# control_prg_03_12_2018.net
KiCad netlist of a schematic drawn in EAGLE
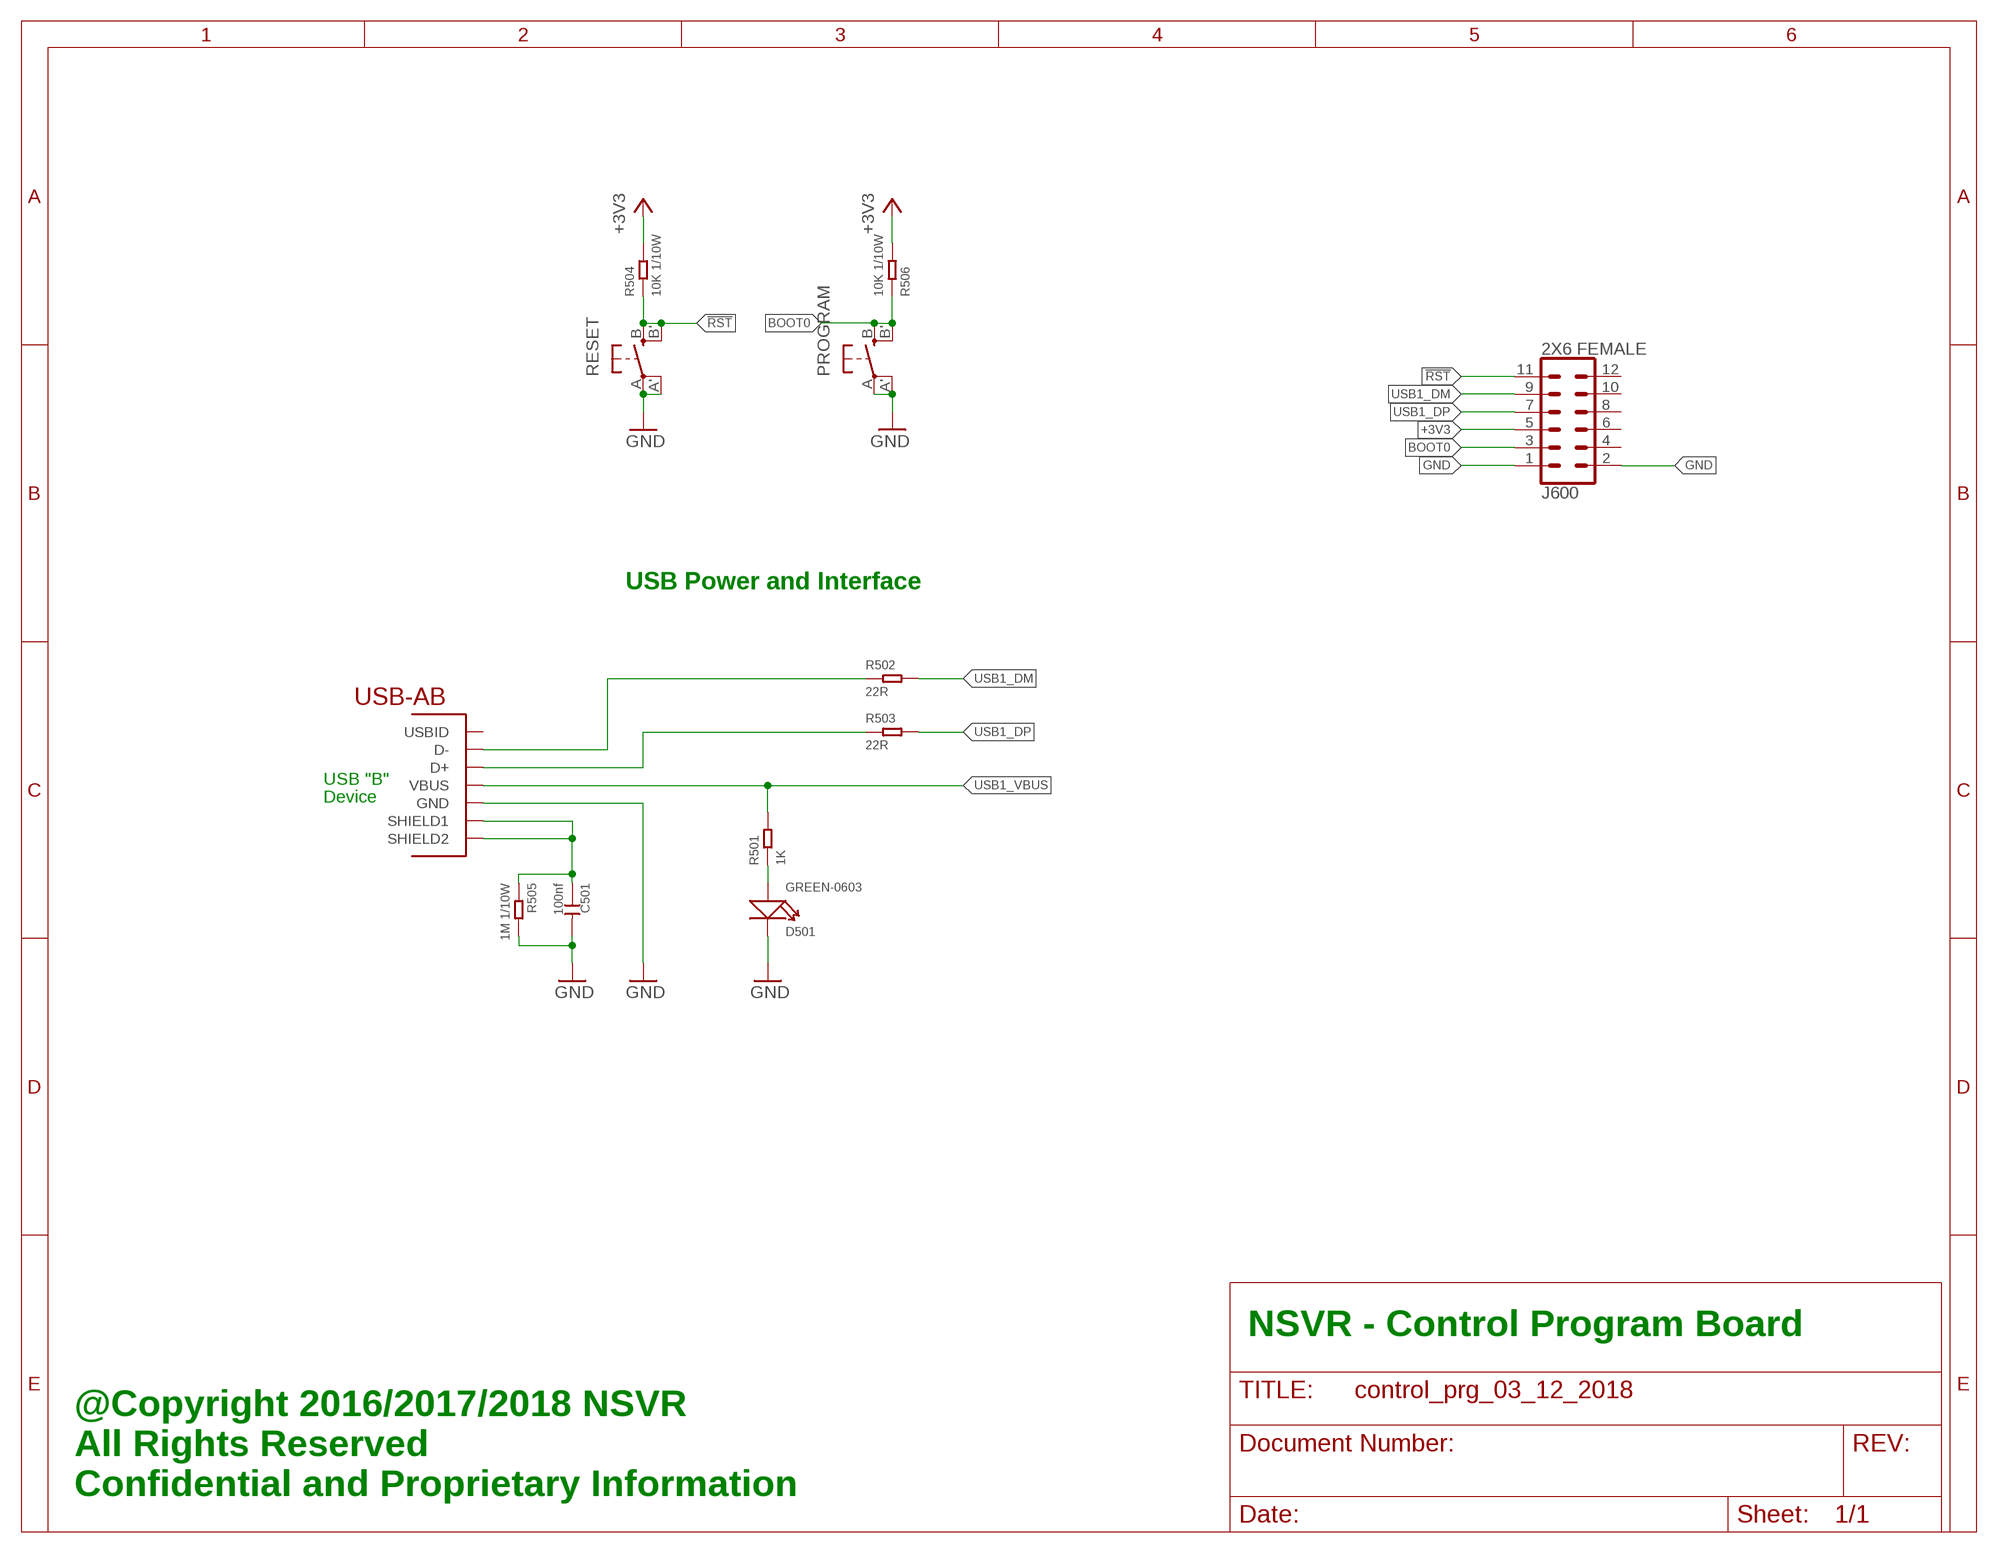
[diagram p0: schematic, sheet 1]

(export (version "E")
  (design (tool "Eeschema 10.0.6"))
  (components
    (comp (ref "C501")
      (value "100nf")
      (footprint "eagle-import:C0603")
      (fields (field (name "MPN") "CC0603KRX7R9BB104"))
      (libsource (lib "eagle-import") (part "CERAMIC-100NF-50V-10%-X7R(0603)"))
    )
    (comp (ref "D501")
      (value "GREEN-0603")
      (footprint "eagle-import:LED-0603")
      (fields (field (name "MPN") "19-217-G7C-AN1P2-3T"))
      (libsource (lib "eagle-import") (part "SMD-LED-CLEAR-GREEN(0603)"))
    )
    (comp (ref "J600")
      (value "2X6 FEMALE")
      (footprint "eagle-import:2X6")
      (libsource (lib "eagle-import") (part "CONN_06X2PTH_FEMALE"))
    )
    (comp (ref "PROGRAM")
      (value "EVQQ2")
      (footprint "eagle-import:EVQ-Q2")
      (libsource (lib "eagle-import") (part "EVQQ2"))
    )
    (comp (ref "R501")
      (value "1K")
      (footprint "eagle-import:R0603")
      (fields (field (name "MPN") "RC0603FR-071KL"))
      (libsource (lib "eagle-import") (part "SMD-RES-1K-1%-1/10W(0603)"))
    )
    (comp (ref "R502")
      (value "22R")
      (footprint "eagle-import:R0603")
      (fields (field (name "MPN") "RC0603JR-0722RL"))
      (libsource (lib "eagle-import") (part "SMD-RES-22R-5%-1/10W(0603)"))
    )
    (comp (ref "R503")
      (value "22R")
      (footprint "eagle-import:R0603")
      (fields (field (name "MPN") "RC0603JR-0722RL"))
      (libsource (lib "eagle-import") (part "SMD-RES-22R-5%-1/10W(0603)"))
    )
    (comp (ref "R504")
      (value "10K 1/10W")
      (footprint "eagle-import:R0603")
      (fields (field (name "MPN") "RC0603JR-0710KL"))
      (libsource (lib "eagle-import") (part "SMD-RES-10K-5%-1/10W(0603)"))
    )
    (comp (ref "R505")
      (value "1M 1/10W")
      (footprint "eagle-import:R0603")
      (fields (field (name "MPN") "RC0603JR-071ML"))
      (libsource (lib "eagle-import") (part "SMD-RES-1M-5%-1/10W(0603)"))
    )
    (comp (ref "R506")
      (value "10K 1/10W")
      (footprint "eagle-import:R0603")
      (fields (field (name "MPN") "RC0603JR-0710KL"))
      (libsource (lib "eagle-import") (part "SMD-RES-10K-5%-1/10W(0603)"))
    )
    (comp (ref "RESET")
      (value "EVQQ2")
      (footprint "eagle-import:EVQ-Q2")
      (libsource (lib "eagle-import") (part "EVQQ2"))
    )
    (comp (ref "USB501")
      (value "USB_AB")
      (footprint "eagle-import:USB-AB-MICRO-SMD")
      (libsource (lib "eagle-import") (part "USB_AB"))
    )
  )
  (nets
    (net (code "1") (name "+3V3") (class "Default")
      (node (ref "J600") (pin "5") (pinfunction "5_5") (pintype "passive"))
      (node (ref "R504") (pin "2") (pinfunction "2_2") (pintype "passive"))
      (node (ref "R506") (pin "2") (pinfunction "2_2") (pintype "passive"))
    )
    (net (code "2") (name "/~{RST}") (class "Default")
      (node (ref "J600") (pin "11") (pinfunction "11_11") (pintype "passive"))
      (node (ref "R504") (pin "1") (pinfunction "1_1") (pintype "passive"))
      (node (ref "RESET") (pin "B") (pinfunction "S_B") (pintype "passive"))
      (node (ref "RESET") (pin "B'") (pinfunction "S1_B'") (pintype "passive"))
    )
    (net (code "3") (name "BOOT0") (class "Default")
      (node (ref "J600") (pin "3") (pinfunction "3_3") (pintype "passive"))
      (node (ref "PROGRAM") (pin "B") (pinfunction "S_B") (pintype "passive"))
      (node (ref "PROGRAM") (pin "B'") (pinfunction "S1_B'") (pintype "passive"))
      (node (ref "R506") (pin "1") (pinfunction "1_1") (pintype "passive"))
    )
    (net (code "4") (name "GND") (class "Default")
      (node (ref "C501") (pin "2") (pinfunction "2_2") (pintype "passive"))
      (node (ref "D501") (pin "-") (pinfunction "-_-") (pintype "passive"))
      (node (ref "J600") (pin "1") (pinfunction "1_1") (pintype "passive"))
      (node (ref "J600") (pin "2") (pinfunction "2_2") (pintype "passive"))
      (node (ref "PROGRAM") (pin "A") (pinfunction "P_A") (pintype "passive"))
      (node (ref "PROGRAM") (pin "A'") (pinfunction "P1_A'") (pintype "passive"))
      (node (ref "R505") (pin "2") (pinfunction "2_2") (pintype "passive"))
      (node (ref "RESET") (pin "A") (pinfunction "P_A") (pintype "passive"))
      (node (ref "RESET") (pin "A'") (pinfunction "P1_A'") (pintype "passive"))
      (node (ref "USB501") (pin "GND") (pinfunction "GND_GND") (pintype "bidirectional"))
    )
    (net (code "5") (name "Net-(C501-Pad1)") (class "Default")
      (node (ref "C501") (pin "1") (pinfunction "1_1") (pintype "passive"))
      (node (ref "R505") (pin "1") (pinfunction "1_1") (pintype "passive"))
      (node (ref "USB501") (pin "SHIELD1") (pinfunction "SHIELD1_SHIELD1") (pintype "bidirectional"))
      (node (ref "USB501") (pin "SHIELD2") (pinfunction "SHIELD2_SHIELD2") (pintype "bidirectional"))
    )
    (net (code "6") (name "Net-(D501-Pad+)") (class "Default")
      (node (ref "D501") (pin "+") (pinfunction "+_+") (pintype "passive"))
      (node (ref "R501") (pin "1") (pinfunction "1_1") (pintype "passive"))
    )
    (net (code "7") (name "Net-(R502-Pad1)") (class "Default")
      (node (ref "R502") (pin "1") (pinfunction "1_1") (pintype "passive"))
      (node (ref "USB501") (pin "D-") (pinfunction "D-_D-") (pintype "bidirectional"))
    )
    (net (code "8") (name "Net-(R503-Pad1)") (class "Default")
      (node (ref "R503") (pin "1") (pinfunction "1_1") (pintype "passive"))
      (node (ref "USB501") (pin "D+") (pinfunction "D+_D+") (pintype "bidirectional"))
    )
    (net (code "9") (name "USB1_DM") (class "Default")
      (node (ref "J600") (pin "9") (pinfunction "9_9") (pintype "passive"))
      (node (ref "R502") (pin "2") (pinfunction "2_2") (pintype "passive"))
    )
    (net (code "10") (name "USB1_DP") (class "Default")
      (node (ref "J600") (pin "7") (pinfunction "7_7") (pintype "passive"))
      (node (ref "R503") (pin "2") (pinfunction "2_2") (pintype "passive"))
    )
    (net (code "11") (name "USB1_VBUS") (class "Default")
      (node (ref "R501") (pin "2") (pinfunction "2_2") (pintype "passive"))
      (node (ref "USB501") (pin "VBUS") (pinfunction "VBUS_VBUS") (pintype "bidirectional"))
    )
    (net (code "12") (name "unconnected-(J600-Pad4)") (class "Default")
      (node (ref "J600") (pin "4") (pinfunction "4_4") (pintype "passive"))
    )
    (net (code "13") (name "unconnected-(J600-Pad6)") (class "Default")
      (node (ref "J600") (pin "6") (pinfunction "6_6") (pintype "passive"))
    )
    (net (code "14") (name "unconnected-(J600-Pad8)") (class "Default")
      (node (ref "J600") (pin "8") (pinfunction "8_8") (pintype "passive"))
    )
    (net (code "15") (name "unconnected-(J600-Pad10)") (class "Default")
      (node (ref "J600") (pin "10") (pinfunction "10_10") (pintype "passive"))
    )
    (net (code "16") (name "unconnected-(J600-Pad12)") (class "Default")
      (node (ref "J600") (pin "12") (pinfunction "12_12") (pintype "passive"))
    )
    (net (code "17") (name "unconnected-(USB501-USBID-PadID)") (class "Default")
      (node (ref "USB501") (pin "ID") (pinfunction "USBID_ID") (pintype "bidirectional"))
    )
  )
)
